# Sch_connectors.net
KiCad netlist of a schematic drawn in Altium Designer
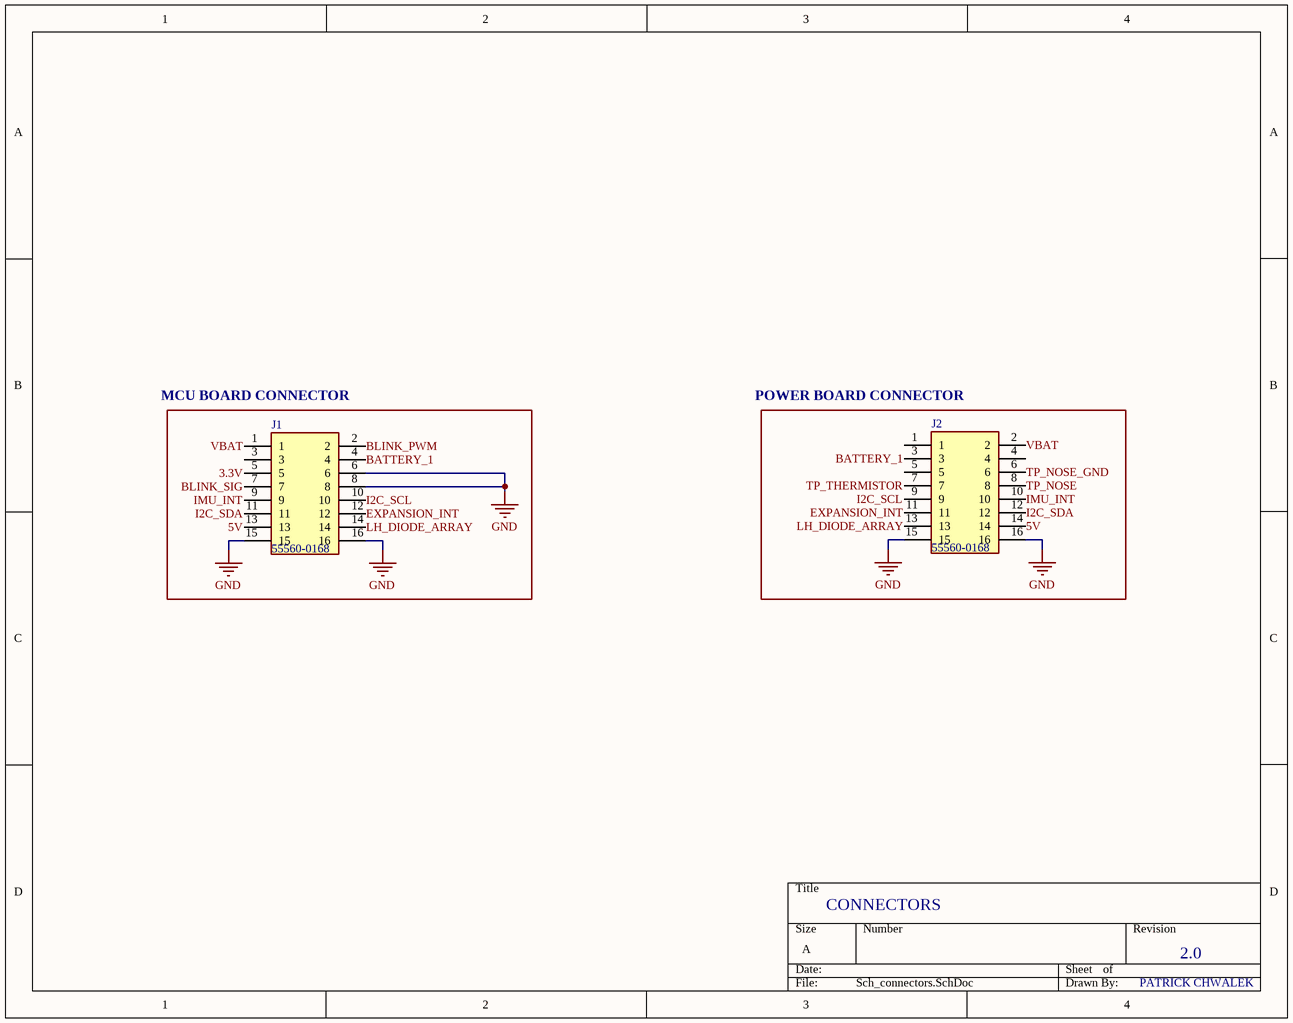
[diagram p0: Sch_connectors.SchDoc]

(export (version "E")
  (design (tool "Eeschema 10.0.6"))
  (components
    (comp (ref "J1")
      (value "55560-0168")
      (footprint "SamacSys:555600168")
      (description "Connector")
      (fields (field (name "MOUSER PART NUMBER") "538-55560-0168") (field (name "RS PART NUMBER") "7206558P"))
      (libsource (lib "*") (part "55560-0168"))
    )
    (comp (ref "J2")
      (value "55560-0168")
      (footprint "SamacSys:555600168")
      (description "Connector")
      (fields (field (name "MOUSER PART NUMBER") "538-55560-0168") (field (name "RS PART NUMBER") "7206558P"))
      (libsource (lib "*") (part "55560-0168"))
    )
  )
  (nets
    (net (code "1") (name "/3.3V") (class "Default")
      (node (ref "J1") (pin "5") (pinfunction "5_5") (pintype "passive"))
    )
    (net (code "2") (name "/5V") (class "Default")
      (node (ref "J1") (pin "13") (pinfunction "13_13") (pintype "passive"))
      (node (ref "J2") (pin "14") (pinfunction "14_14") (pintype "passive"))
    )
    (net (code "3") (name "/BATTERY_1") (class "Default")
      (node (ref "J1") (pin "4") (pinfunction "4_4") (pintype "passive"))
      (node (ref "J2") (pin "3") (pinfunction "3_3") (pintype "passive"))
    )
    (net (code "4") (name "/BLINK_PWM") (class "Default")
      (node (ref "J1") (pin "2") (pinfunction "2_2") (pintype "passive"))
    )
    (net (code "5") (name "/BLINK_SIG") (class "Default")
      (node (ref "J1") (pin "7") (pinfunction "7_7") (pintype "passive"))
    )
    (net (code "6") (name "/EXPANSION_INT") (class "Default")
      (node (ref "J1") (pin "12") (pinfunction "12_12") (pintype "passive"))
      (node (ref "J2") (pin "11") (pinfunction "11_11") (pintype "passive"))
    )
    (net (code "7") (name "/I2C_SCL") (class "Default")
      (node (ref "J1") (pin "10") (pinfunction "10_10") (pintype "passive"))
      (node (ref "J2") (pin "9") (pinfunction "9_9") (pintype "passive"))
    )
    (net (code "8") (name "/I2C_SDA") (class "Default")
      (node (ref "J1") (pin "11") (pinfunction "11_11") (pintype "passive"))
      (node (ref "J2") (pin "12") (pinfunction "12_12") (pintype "passive"))
    )
    (net (code "9") (name "/IMU_INT") (class "Default")
      (node (ref "J1") (pin "9") (pinfunction "9_9") (pintype "passive"))
      (node (ref "J2") (pin "10") (pinfunction "10_10") (pintype "passive"))
    )
    (net (code "10") (name "/LH_DIODE_ARRAY") (class "Default")
      (node (ref "J1") (pin "14") (pinfunction "14_14") (pintype "passive"))
      (node (ref "J2") (pin "13") (pinfunction "13_13") (pintype "passive"))
    )
    (net (code "11") (name "/TP_NOSE") (class "Default")
      (node (ref "J2") (pin "8") (pinfunction "8_8") (pintype "passive"))
    )
    (net (code "12") (name "/TP_NOSE_GND") (class "Default")
      (node (ref "J2") (pin "6") (pinfunction "6_6") (pintype "passive"))
    )
    (net (code "13") (name "/TP_THERMISTOR") (class "Default")
      (node (ref "J2") (pin "7") (pinfunction "7_7") (pintype "passive"))
    )
    (net (code "14") (name "/VBAT") (class "Default")
      (node (ref "J1") (pin "1") (pinfunction "1_1") (pintype "passive"))
      (node (ref "J2") (pin "2") (pinfunction "2_2") (pintype "passive"))
    )
    (net (code "15") (name "GND") (class "Default")
      (node (ref "J1") (pin "15") (pinfunction "15_15") (pintype "passive"))
      (node (ref "J1") (pin "16") (pinfunction "16_16") (pintype "passive"))
      (node (ref "J1") (pin "6") (pinfunction "6_6") (pintype "passive"))
      (node (ref "J1") (pin "8") (pinfunction "8_8") (pintype "passive"))
      (node (ref "J2") (pin "15") (pinfunction "15_15") (pintype "passive"))
      (node (ref "J2") (pin "16") (pinfunction "16_16") (pintype "passive"))
    )
    (net (code "16") (name "unconnected-(J1-Pad3)") (class "Default")
      (node (ref "J1") (pin "3") (pinfunction "3_3") (pintype "passive"))
    )
    (net (code "17") (name "unconnected-(J2-Pad1)") (class "Default")
      (node (ref "J2") (pin "1") (pinfunction "1_1") (pintype "passive"))
    )
    (net (code "18") (name "unconnected-(J2-Pad4)") (class "Default")
      (node (ref "J2") (pin "4") (pinfunction "4_4") (pintype "passive"))
    )
    (net (code "19") (name "unconnected-(J2-Pad5)") (class "Default")
      (node (ref "J2") (pin "5") (pinfunction "5_5") (pintype "passive"))
    )
  )
)
